# Auto20.net
KiCad netlist of a schematic drawn in EAGLE
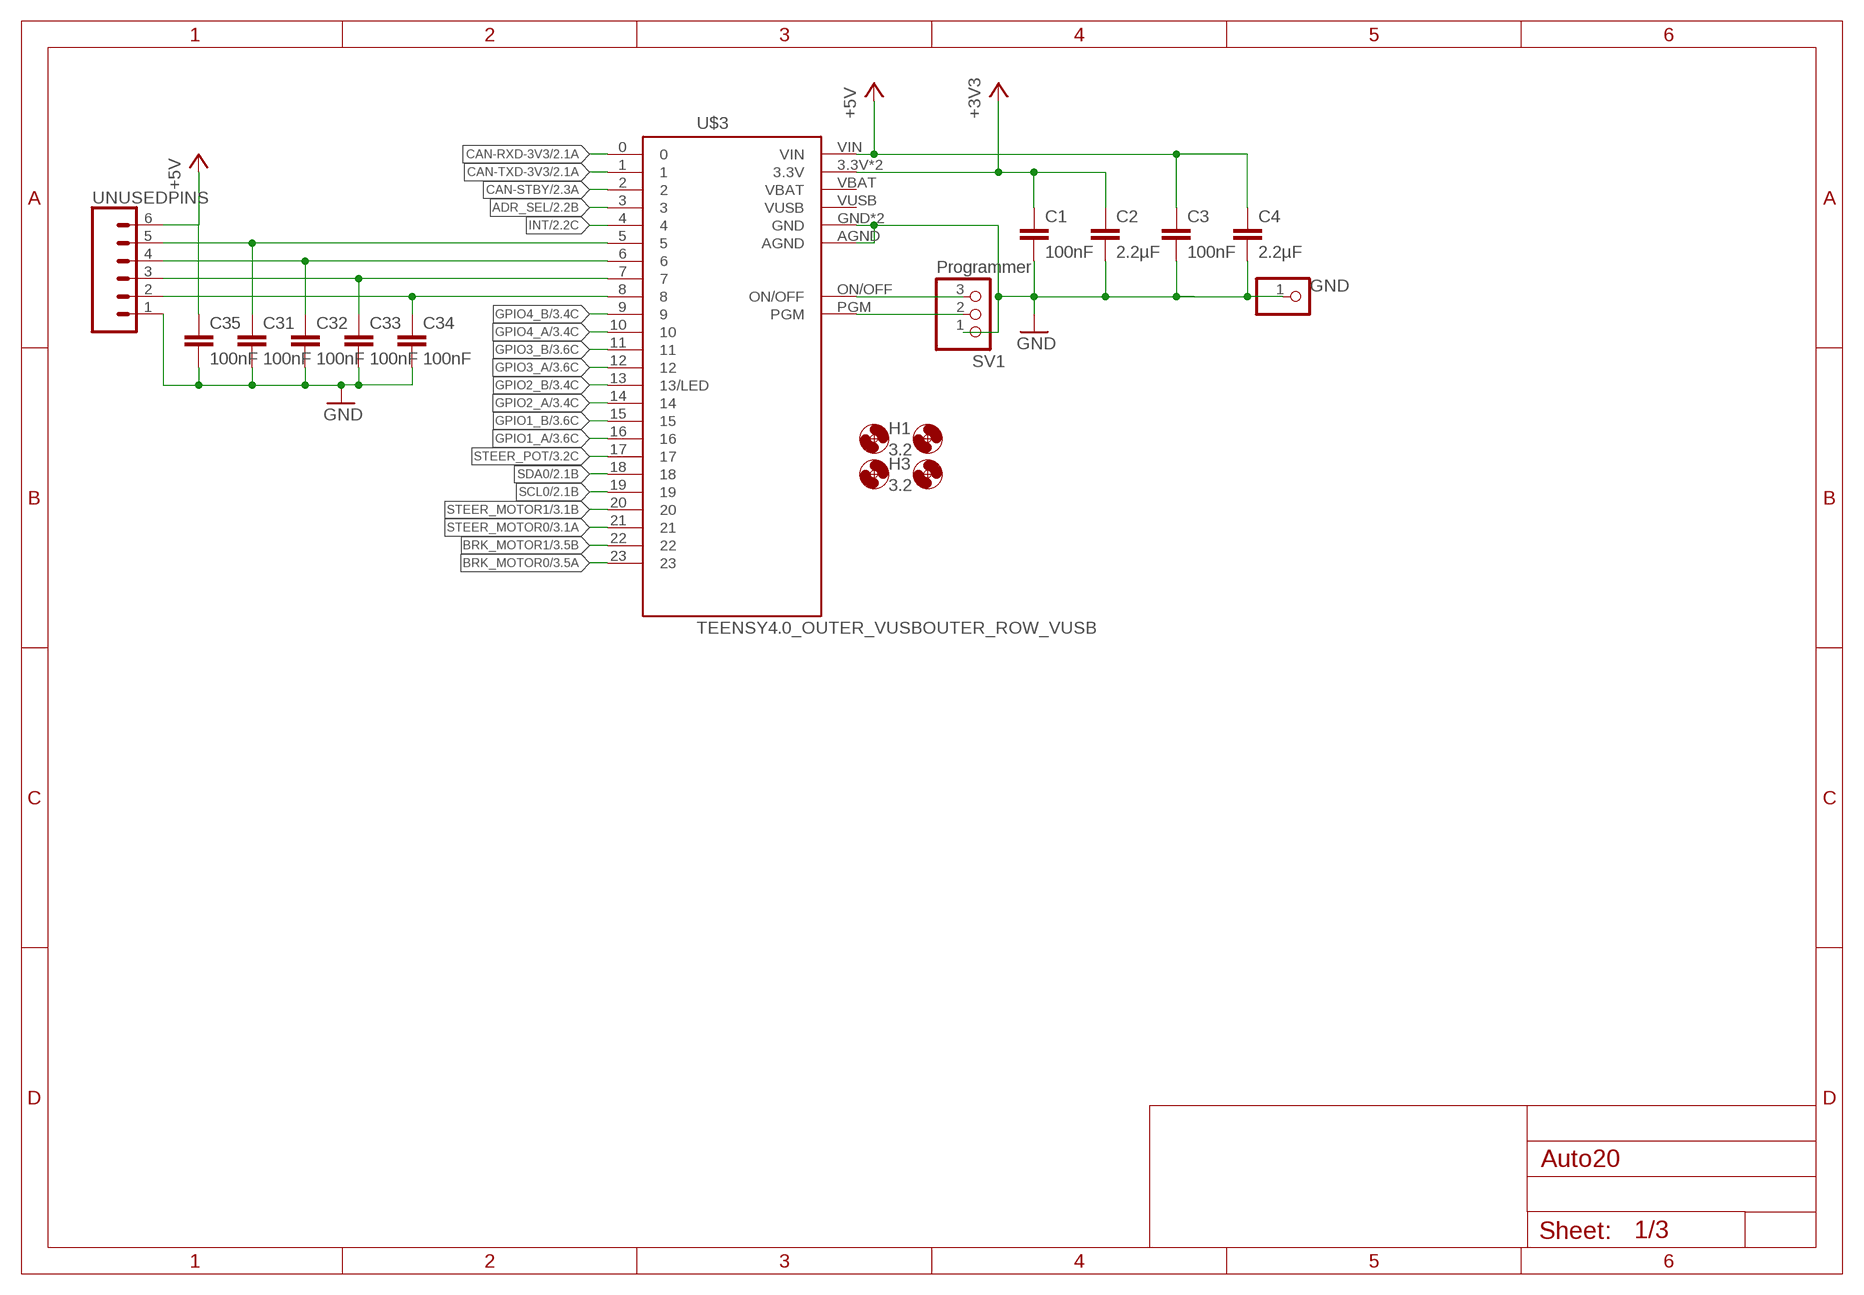
[diagram p0: schematic, sheet 1]
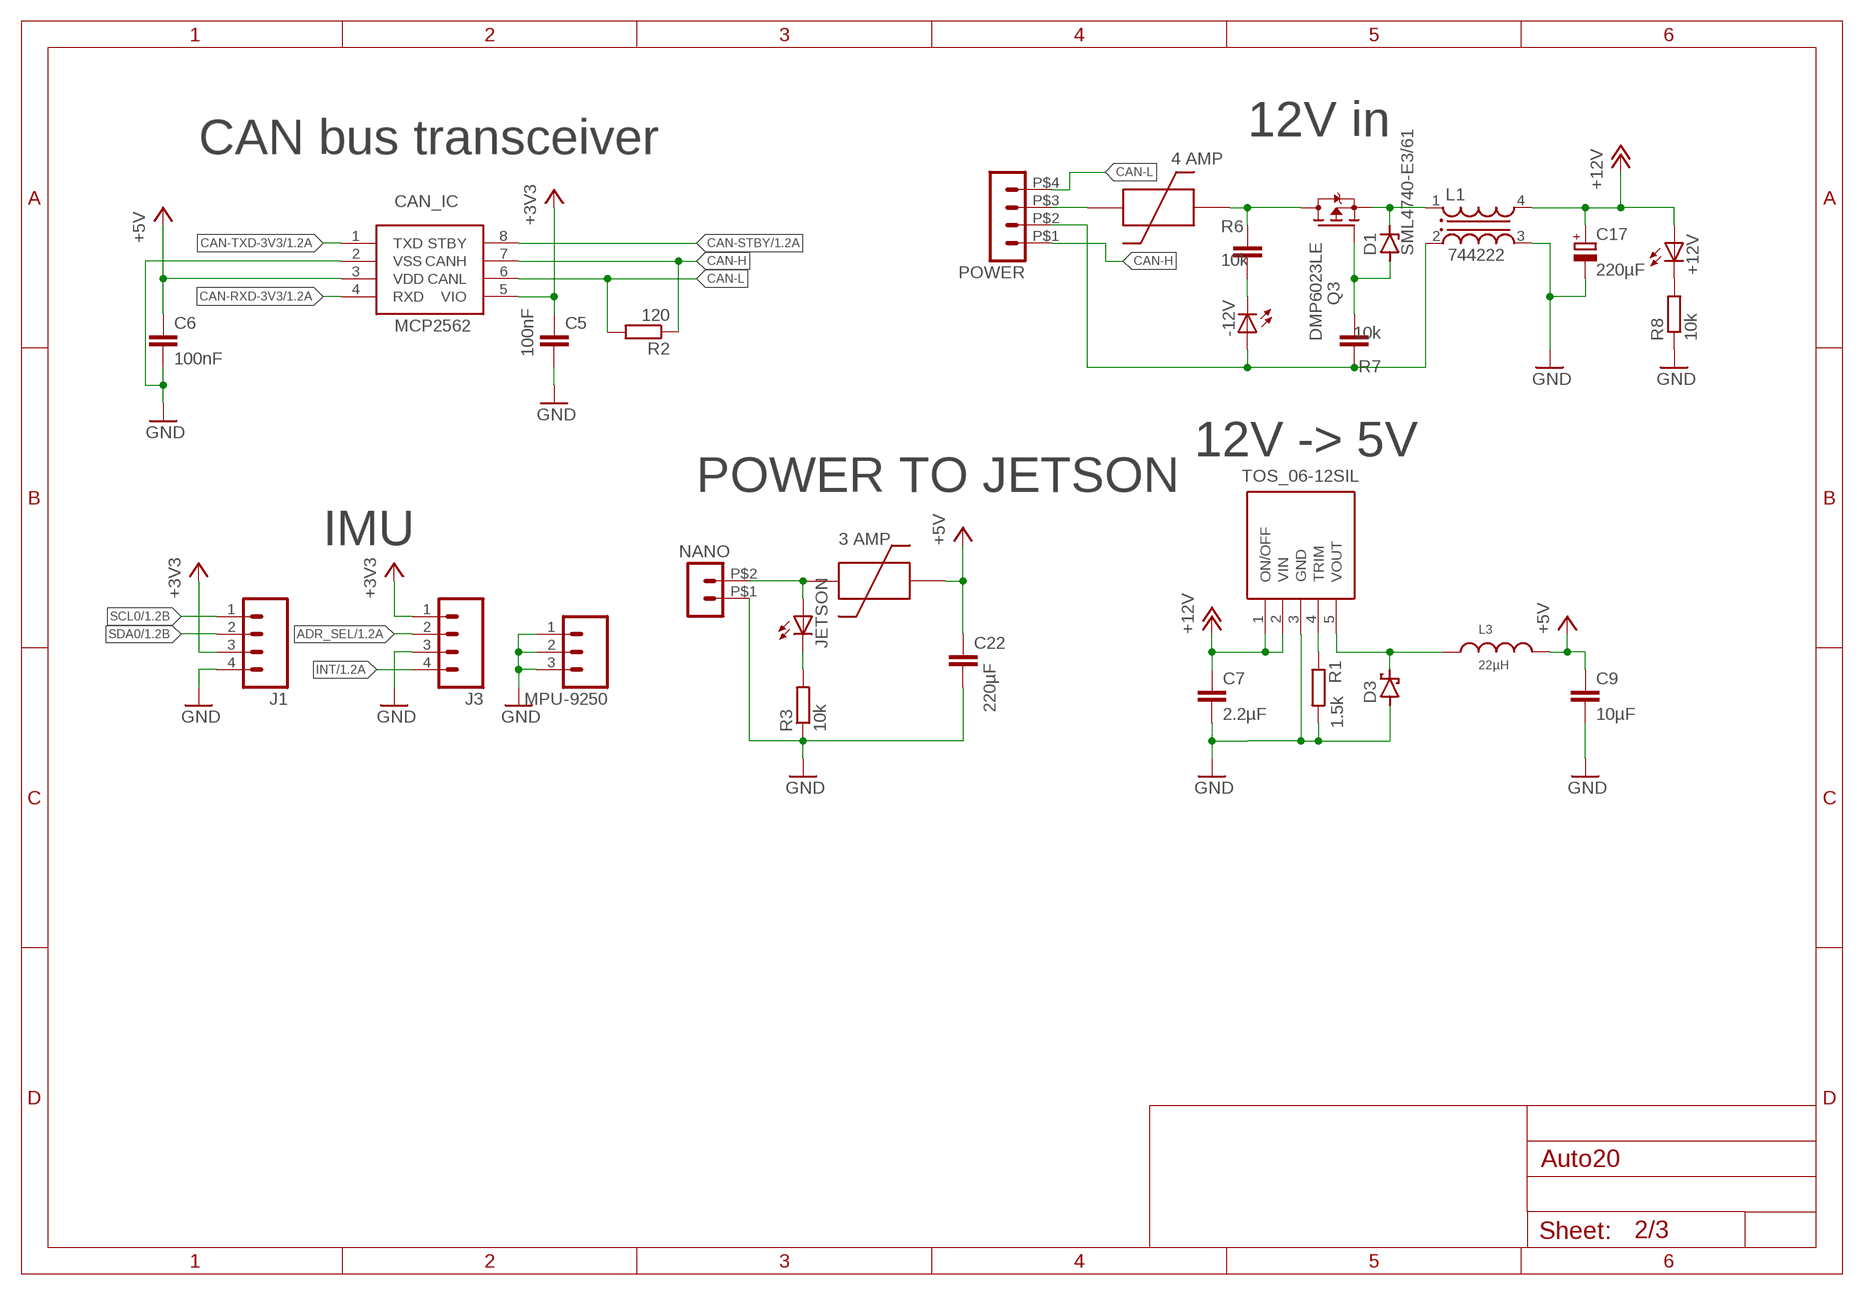
[diagram p1: schematic, sheet 2]
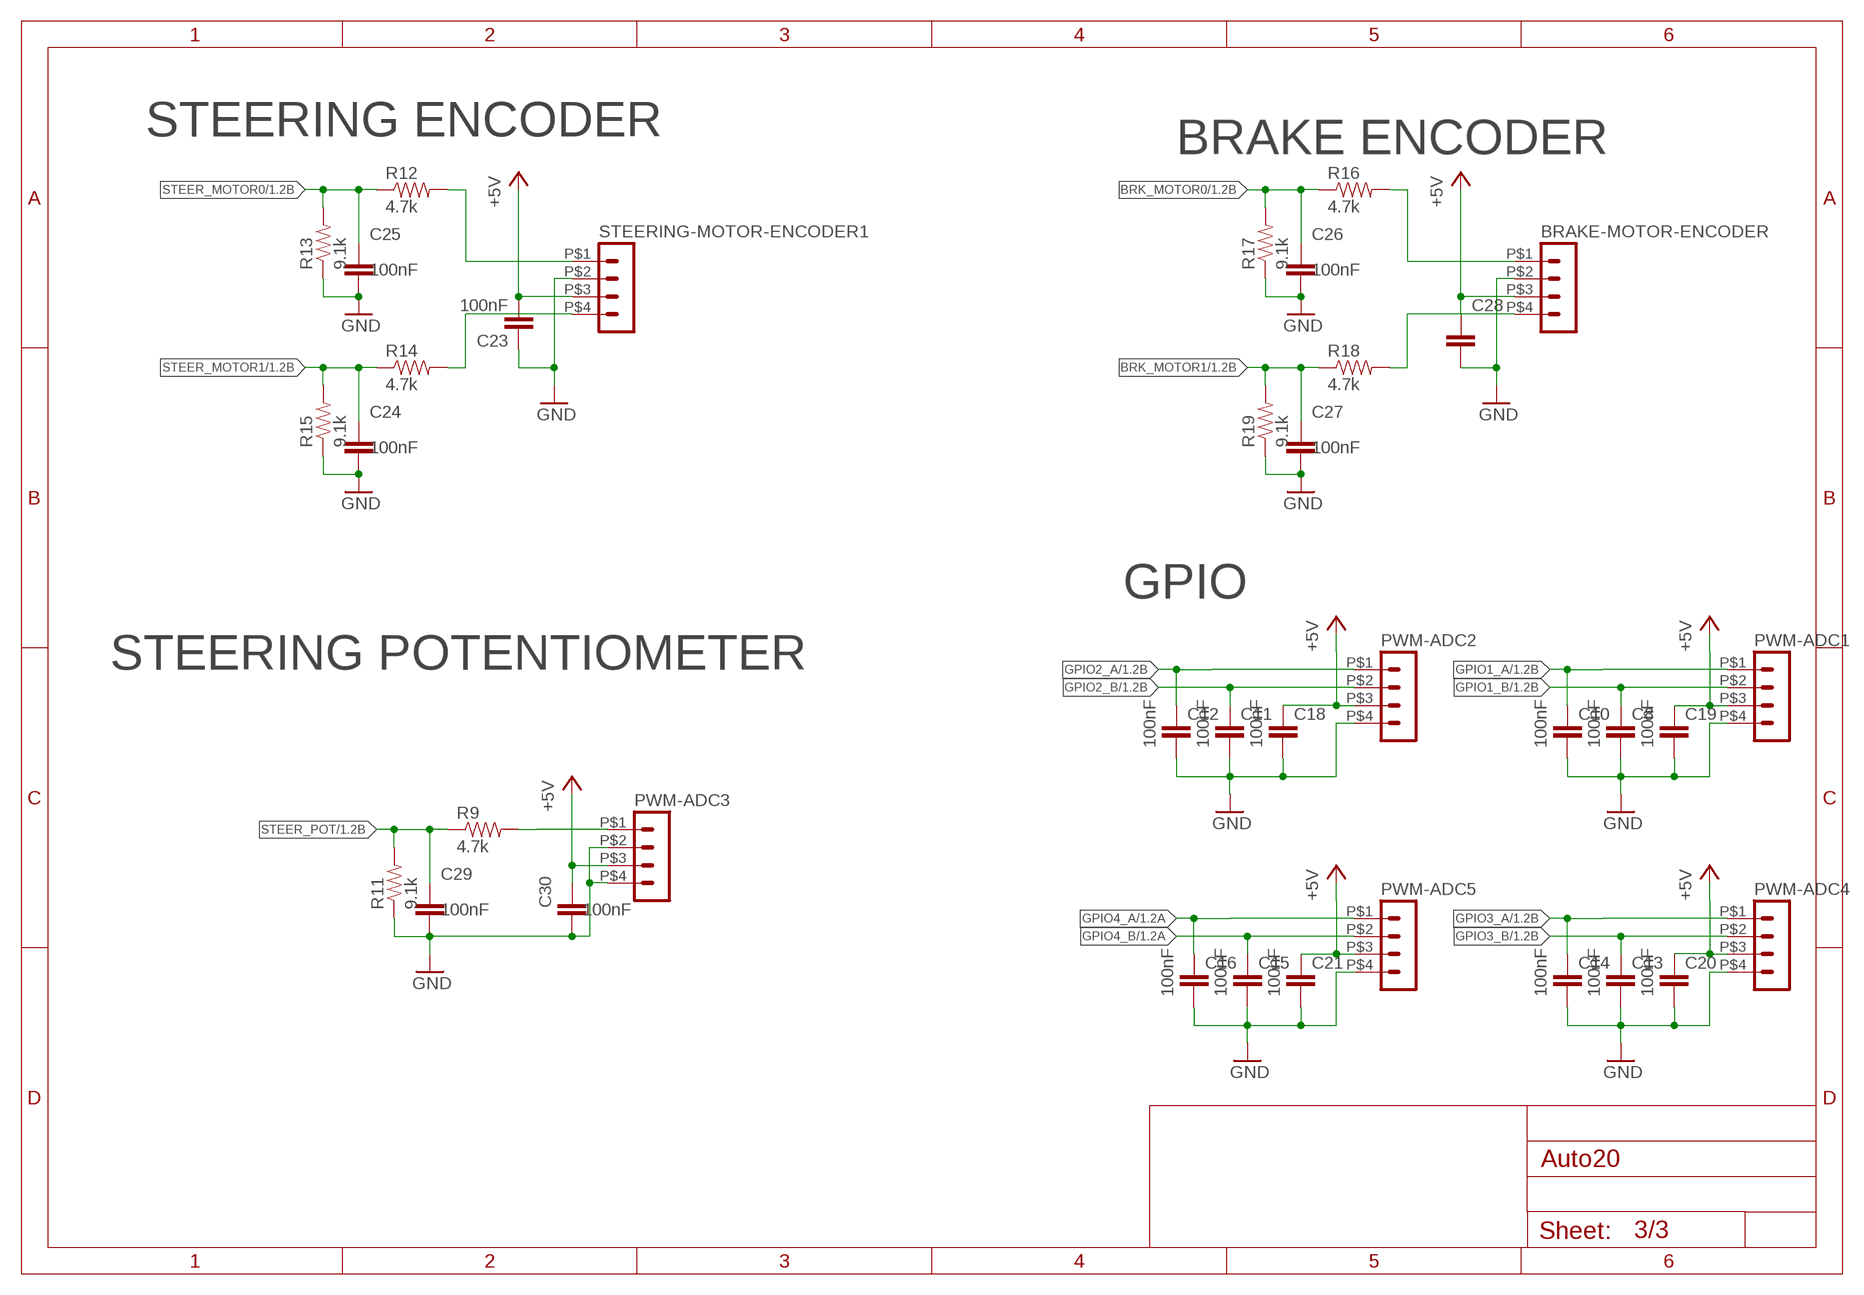
[diagram p2: schematic, sheet 3]

(export (version "E")
  (design (tool "Eeschema 10.0.6"))
  (components
    (comp (ref "+12V")
      (value "LEDSMT1206")
      (footprint "eagle-import:1206")
      (libsource (lib "eagle-import") (part "LEDSMT1206"))
    )
    (comp (ref "-12V")
      (value "LEDSMT1206")
      (footprint "eagle-import:1206")
      (libsource (lib "eagle-import") (part "LEDSMT1206"))
    )
    (comp (ref "C5")
      (value "100nF")
      (footprint "eagle-import:RESC0805_L")
      (libsource (lib "eagle-import") (part "CAPACITOR_0805_L"))
    )
    (comp (ref "C6")
      (value "100nF")
      (footprint "eagle-import:RESC0805_L")
      (libsource (lib "eagle-import") (part "CAPACITOR_0805_L"))
    )
    (comp (ref "C7")
      (value "2.2µF")
      (footprint "eagle-import:C1210")
      (libsource (lib "eagle-import") (part "C-EUC1210"))
    )
    (comp (ref "C9")
      (value "10µF")
      (footprint "eagle-import:C1210")
      (libsource (lib "eagle-import") (part "C-EUC1210"))
    )
    (comp (ref "C17")
      (value "220µF")
      (footprint "eagle-import:PANASONIC_E")
      (libsource (lib "eagle-import") (part "CPOL-EUE"))
    )
    (comp (ref "C22")
      (value "220µF")
      (footprint "eagle-import:C1210")
      (libsource (lib "eagle-import") (part "resistor_348_C-EUC1210"))
    )
    (comp (ref "CAN_IC")
      (value "MCP2562")
      (footprint "eagle-import:SOIC127P600X175-8")
      (libsource (lib "eagle-import") (part "MCP2562"))
    )
    (comp (ref "D1")
      (value "SML4740-E3/61")
      (footprint "eagle-import:DO214AC")
      (libsource (lib "eagle-import") (part "ZENERSMA"))
    )
    (comp (ref "D3")
      (value "SBR1U150SA")
      (footprint "eagle-import:DO214AC")
      (libsource (lib "eagle-import") (part "SBRSMA"))
    )
    (comp (ref "IC1")
      (value "TOS_06-12SIL")
      (footprint "eagle-import:TOS-06-12SIL-6A")
      (fields
        (field (name "MANUFACTURER_PART_NUMBER") "TOS 06-12SIL")
        (field (name "RS_PART_NUMBER") "7066432")
      )
      (libsource (lib "eagle-import") (part "TOS_06-12SIL"))
    )
    (comp (ref "J1")
      (value "M04PTH")
      (footprint "eagle-import:1X04")
      (libsource (lib "eagle-import") (part "M04PTH"))
    )
    (comp (ref "J3")
      (value "M04PTH")
      (footprint "eagle-import:1X04")
      (libsource (lib "eagle-import") (part "M04PTH"))
    )
    (comp (ref "JETSON")
      (value "LEDSMT1206")
      (footprint "eagle-import:1206")
      (libsource (lib "eagle-import") (part "LEDSMT1206"))
    )
    (comp (ref "L1")
      (value "744222")
      (footprint "eagle-import:WE-SL2")
      (libsource (lib "eagle-import") (part "WE-SL2_744222"))
    )
    (comp (ref "L3")
      (value "22µH")
      (footprint "eagle-import:WE-PD_7332_7345_PLASTIC_BASE")
      (libsource (lib "eagle-import") (part "WE-PD_7345_PLASTIC_7447779122"))
    )
    (comp (ref "MPU-9250")
      (value "M03PTH")
      (footprint "eagle-import:1X03")
      (libsource (lib "eagle-import") (part "M03PTH"))
    )
    (comp (ref "NANO")
      (value "HEADER_POS2_43045-0200")
      (footprint "eagle-import:43045-0200")
      (libsource (lib "eagle-import") (part "HEADER_POS2_?43045-0200"))
    )
    (comp (ref "POWER")
      (value "HEADER_POS4_43045-0401")
      (footprint "eagle-import:43045-0400")
      (libsource (lib "eagle-import") (part "HEADER_POS4_?43045-0401"))
    )
    (comp (ref "Q3")
      (value "DMP6023LE")
      (footprint "eagle-import:SOT223")
      (libsource (lib "eagle-import") (part "BSP170P"))
    )
    (comp (ref "R1")
      (value "1.5k")
      (footprint "eagle-import:R0805")
      (libsource (lib "eagle-import") (part "R-EU_R0805"))
    )
    (comp (ref "R2")
      (value "120")
      (footprint "eagle-import:R0603")
      (libsource (lib "eagle-import") (part "R-EU_R0603"))
    )
    (comp (ref "R3")
      (value "10k")
      (footprint "eagle-import:R0805")
      (libsource (lib "eagle-import") (part "R-EU_R0805"))
    )
    (comp (ref "R6")
      (value "10k")
      (footprint "eagle-import:RESC0805_L")
      (libsource (lib "eagle-import") (part "CAPACITOR_0805_L"))
    )
    (comp (ref "R7")
      (value "10k")
      (footprint "eagle-import:RESC0805_L")
      (libsource (lib "eagle-import") (part "CAPACITOR_0805_L"))
    )
    (comp (ref "R8")
      (value "10k")
      (footprint "eagle-import:R0805")
      (libsource (lib "eagle-import") (part "R-EU_R0805"))
    )
    (comp (ref "U$1")
      (value "SMF_OMNI-BLOK_FUSE_BLOCK")
      (footprint "eagle-import:SMF_OMNI-BLOK_FUSE_BLOCK")
      (libsource (lib "eagle-import") (part "SMF_OMNI-BLOK_FUSE_BLOCK"))
    )
    (comp (ref "U$2")
      (value "SMF_OMNI-BLOK_FUSE_BLOCK")
      (footprint "eagle-import:SMF_OMNI-BLOK_FUSE_BLOCK")
      (libsource (lib "eagle-import") (part "SMF_OMNI-BLOK_FUSE_BLOCK"))
    )
    (comp (ref "BRAKE-MOTOR-ENCODER")
      (value "HEADER_POS4_43045-0401")
      (footprint "eagle-import:43045-0400")
      (libsource (lib "eagle-import") (part "HEADER_POS4_?43045-0401"))
    )
    (comp (ref "C8")
      (value "100nF")
      (footprint "eagle-import:RESC0805_L")
      (libsource (lib "eagle-import") (part "CAPACITOR_0805_L"))
    )
    (comp (ref "C10")
      (value "100nF")
      (footprint "eagle-import:RESC0805_L")
      (libsource (lib "eagle-import") (part "CAPACITOR_0805_L"))
    )
    (comp (ref "C11")
      (value "100nF")
      (footprint "eagle-import:RESC0805_L")
      (libsource (lib "eagle-import") (part "CAPACITOR_0805_L"))
    )
    (comp (ref "C12")
      (value "100nF")
      (footprint "eagle-import:RESC0805_L")
      (libsource (lib "eagle-import") (part "CAPACITOR_0805_L"))
    )
    (comp (ref "C13")
      (value "100nF")
      (footprint "eagle-import:RESC0805_L")
      (libsource (lib "eagle-import") (part "CAPACITOR_0805_L"))
    )
    (comp (ref "C14")
      (value "100nF")
      (footprint "eagle-import:RESC0805_L")
      (libsource (lib "eagle-import") (part "CAPACITOR_0805_L"))
    )
    (comp (ref "C15")
      (value "100nF")
      (footprint "eagle-import:RESC0805_L")
      (libsource (lib "eagle-import") (part "CAPACITOR_0805_L"))
    )
    (comp (ref "C16")
      (value "100nF")
      (footprint "eagle-import:RESC0805_L")
      (libsource (lib "eagle-import") (part "CAPACITOR_0805_L"))
    )
    (comp (ref "C18")
      (value "100nF")
      (footprint "eagle-import:RESC0805_L")
      (libsource (lib "eagle-import") (part "CAPACITOR_0805_L"))
    )
    (comp (ref "C19")
      (value "100nF")
      (footprint "eagle-import:RESC0805_L")
      (libsource (lib "eagle-import") (part "CAPACITOR_0805_L"))
    )
    (comp (ref "C20")
      (value "100nF")
      (footprint "eagle-import:RESC0805_L")
      (libsource (lib "eagle-import") (part "CAPACITOR_0805_L"))
    )
    (comp (ref "C21")
      (value "100nF")
      (footprint "eagle-import:RESC0805_L")
      (libsource (lib "eagle-import") (part "CAPACITOR_0805_L"))
    )
    (comp (ref "C23")
      (value "100nF")
      (footprint "eagle-import:RESC0805_L")
      (libsource (lib "eagle-import") (part "CAPACITOR_0805_L"))
    )
    (comp (ref "C24")
      (value "100nF")
      (footprint "eagle-import:RESC0805_L")
      (libsource (lib "eagle-import") (part "CAPACITOR_0805_L"))
    )
    (comp (ref "C25")
      (value "100nF")
      (footprint "eagle-import:RESC0805_L")
      (libsource (lib "eagle-import") (part "CAPACITOR_0805_L"))
    )
    (comp (ref "C26")
      (value "100nF")
      (footprint "eagle-import:RESC0805_L")
      (libsource (lib "eagle-import") (part "CAPACITOR_0805_L"))
    )
    (comp (ref "C27")
      (value "100nF")
      (footprint "eagle-import:RESC0805_L")
      (libsource (lib "eagle-import") (part "CAPACITOR_0805_L"))
    )
    (comp (ref "C28")
      (value "100nF")
      (footprint "eagle-import:RESC0805_L")
      (libsource (lib "eagle-import") (part "CAPACITOR_0805_L"))
    )
    (comp (ref "C29")
      (value "100nF")
      (footprint "eagle-import:RESC0805_L")
      (libsource (lib "eagle-import") (part "CAPACITOR_0805_L"))
    )
    (comp (ref "C30")
      (value "100nF")
      (footprint "eagle-import:RESC0805_L")
      (libsource (lib "eagle-import") (part "CAPACITOR_0805_L"))
    )
    (comp (ref "PWM-ADC1")
      (value "HEADER_POS4_43045-0401")
      (footprint "eagle-import:43045-0400")
      (libsource (lib "eagle-import") (part "HEADER_POS4_?43045-0401"))
    )
    (comp (ref "PWM-ADC2")
      (value "HEADER_POS4_43045-0401")
      (footprint "eagle-import:43045-0400")
      (libsource (lib "eagle-import") (part "HEADER_POS4_?43045-0401"))
    )
    (comp (ref "PWM-ADC3")
      (value "HEADER_POS4_43045-0401")
      (footprint "eagle-import:43045-0400")
      (libsource (lib "eagle-import") (part "HEADER_POS4_?43045-0401"))
    )
    (comp (ref "PWM-ADC4")
      (value "HEADER_POS4_43045-0401")
      (footprint "eagle-import:43045-0400")
      (libsource (lib "eagle-import") (part "HEADER_POS4_?43045-0401"))
    )
    (comp (ref "PWM-ADC5")
      (value "HEADER_POS4_43045-0401")
      (footprint "eagle-import:43045-0400")
      (libsource (lib "eagle-import") (part "HEADER_POS4_?43045-0401"))
    )
    (comp (ref "R9")
      (value "4.7k")
      (footprint "eagle-import:0805")
      (libsource (lib "eagle-import") (part "RESISTOR0805-RES"))
    )
    (comp (ref "R11")
      (value "9.1k")
      (footprint "eagle-import:0805")
      (libsource (lib "eagle-import") (part "RESISTOR0805-RES"))
    )
    (comp (ref "R12")
      (value "4.7k")
      (footprint "eagle-import:0805")
      (libsource (lib "eagle-import") (part "RESISTOR0805-RES"))
    )
    (comp (ref "R13")
      (value "9.1k")
      (footprint "eagle-import:0805")
      (libsource (lib "eagle-import") (part "RESISTOR0805-RES"))
    )
    (comp (ref "R14")
      (value "4.7k")
      (footprint "eagle-import:0805")
      (libsource (lib "eagle-import") (part "RESISTOR0805-RES"))
    )
    (comp (ref "R15")
      (value "9.1k")
      (footprint "eagle-import:0805")
      (libsource (lib "eagle-import") (part "RESISTOR0805-RES"))
    )
    (comp (ref "R16")
      (value "4.7k")
      (footprint "eagle-import:0805")
      (libsource (lib "eagle-import") (part "RESISTOR0805-RES"))
    )
    (comp (ref "R17")
      (value "9.1k")
      (footprint "eagle-import:0805")
      (libsource (lib "eagle-import") (part "RESISTOR0805-RES"))
    )
    (comp (ref "R18")
      (value "4.7k")
      (footprint "eagle-import:0805")
      (libsource (lib "eagle-import") (part "RESISTOR0805-RES"))
    )
    (comp (ref "R19")
      (value "9.1k")
      (footprint "eagle-import:0805")
      (libsource (lib "eagle-import") (part "RESISTOR0805-RES"))
    )
    (comp (ref "STEERING-MOTOR-ENCODER1")
      (value "HEADER_POS4_43045-0401")
      (footprint "eagle-import:43045-0400")
      (libsource (lib "eagle-import") (part "HEADER_POS4_?43045-0401"))
    )
    (comp (ref "C1")
      (value "100nF")
      (footprint "eagle-import:RESC0805_L")
      (libsource (lib "eagle-import") (part "CAPACITOR_0805_L"))
    )
    (comp (ref "C2")
      (value "2.2µF")
      (footprint "eagle-import:C1210")
      (libsource (lib "eagle-import") (part "C-EUC1210"))
    )
    (comp (ref "C3")
      (value "100nF")
      (footprint "eagle-import:RESC0805_L")
      (libsource (lib "eagle-import") (part "CAPACITOR_0805_L"))
    )
    (comp (ref "C4")
      (value "2.2µF")
      (footprint "eagle-import:C1210")
      (libsource (lib "eagle-import") (part "C-EUC1210"))
    )
    (comp (ref "C31")
      (value "100nF")
      (footprint "eagle-import:RESC0805_L")
      (libsource (lib "eagle-import") (part "CAPACITOR_0805_L"))
    )
    (comp (ref "C32")
      (value "100nF")
      (footprint "eagle-import:RESC0805_L")
      (libsource (lib "eagle-import") (part "CAPACITOR_0805_L"))
    )
    (comp (ref "C33")
      (value "100nF")
      (footprint "eagle-import:RESC0805_L")
      (libsource (lib "eagle-import") (part "CAPACITOR_0805_L"))
    )
    (comp (ref "C34")
      (value "100nF")
      (footprint "eagle-import:RESC0805_L")
      (libsource (lib "eagle-import") (part "CAPACITOR_0805_L"))
    )
    (comp (ref "C35")
      (value "100nF")
      (footprint "eagle-import:RESC0805_L")
      (libsource (lib "eagle-import") (part "CAPACITOR_0805_L"))
    )
    (comp (ref "GND")
      (value "PINHD-1X1")
      (footprint "eagle-import:1X01")
      (libsource (lib "eagle-import") (part "PINHD-1X1"))
    )
    (comp (ref "H1")
      (value "3.2")
      (footprint "eagle-import:3,2")
      (libsource (lib "eagle-import") (part "MOUNT-HOLE3.2"))
    )
    (comp (ref "H2")
      (value "3.2")
      (footprint "eagle-import:3,2")
      (libsource (lib "eagle-import") (part "MOUNT-HOLE3.2"))
    )
    (comp (ref "H3")
      (value "3.2")
      (footprint "eagle-import:3,2")
      (libsource (lib "eagle-import") (part "MOUNT-HOLE3.2"))
    )
    (comp (ref "H4")
      (value "3.2")
      (footprint "eagle-import:3,2")
      (libsource (lib "eagle-import") (part "MOUNT-HOLE3.2"))
    )
    (comp (ref "SV1")
      (value "Programmer")
      (footprint "eagle-import:1X03")
      (libsource (lib "eagle-import") (part "PINHD-1X3"))
    )
    (comp (ref "U$3")
      (value "TEENSY4.0_OUTER_VUSBOUTER_ROW_VUSB")
      (footprint "eagle-import:TEENSY_4.0_OUTER_VUSB")
      (libsource (lib "eagle-import") (part "TEENSY4.0_OUTER_VUSBOUTER_ROW_VUSB"))
    )
    (comp (ref "UNUSEDPINS")
      (value "CONN_06LOCK")
      (footprint "eagle-import:1X06_LOCK")
      (libsource (lib "eagle-import") (part "CONN_06LOCK"))
    )
  )
  (nets
    (net (code "1") (name "+3V3") (class "Default")
      (node (ref "C1") (pin "1") (pinfunction "1_1") (pintype "passive"))
      (node (ref "C2") (pin "1") (pinfunction "1_1") (pintype "passive"))
      (node (ref "C5") (pin "1") (pinfunction "1_1") (pintype "passive"))
      (node (ref "CAN_IC") (pin "5") (pinfunction "VIO_5") (pintype "input"))
      (node (ref "J1") (pin "3") (pinfunction "3_3") (pintype "passive"))
      (node (ref "J3") (pin "1") (pinfunction "1_1") (pintype "passive"))
      (node (ref "U$3") (pin "3.3V") (pinfunction "3.3V_3.3V") (pintype "bidirectional"))
      (node (ref "U$3") (pin "3.3V1") (pinfunction "3.3V_3.3V1") (pintype "bidirectional"))
    )
    (net (code "2") (name "+5V") (class "Default")
      (node (ref "BRAKE-MOTOR-ENCODER") (pin "P$3") (pinfunction "3_P$3") (pintype "passive"))
      (node (ref "C18") (pin "1") (pinfunction "1_1") (pintype "passive"))
      (node (ref "C19") (pin "1") (pinfunction "1_1") (pintype "passive"))
      (node (ref "C20") (pin "1") (pinfunction "1_1") (pintype "passive"))
      (node (ref "C21") (pin "1") (pinfunction "1_1") (pintype "passive"))
      (node (ref "C22") (pin "1") (pinfunction "1_1") (pintype "passive"))
      (node (ref "C23") (pin "2") (pinfunction "2_2") (pintype "passive"))
      (node (ref "C28") (pin "1") (pinfunction "1_1") (pintype "passive"))
      (node (ref "C3") (pin "1") (pinfunction "1_1") (pintype "passive"))
      (node (ref "C30") (pin "1") (pinfunction "1_1") (pintype "passive"))
      (node (ref "C35") (pin "1") (pinfunction "1_1") (pintype "passive"))
      (node (ref "C4") (pin "1") (pinfunction "1_1") (pintype "passive"))
      (node (ref "C6") (pin "1") (pinfunction "1_1") (pintype "passive"))
      (node (ref "C9") (pin "1") (pinfunction "1_1") (pintype "passive"))
      (node (ref "CAN_IC") (pin "3") (pinfunction "VDD_3") (pintype "power_in"))
      (node (ref "L3") (pin "2") (pinfunction "2_2") (pintype "passive"))
      (node (ref "PWM-ADC1") (pin "P$3") (pinfunction "3_P$3") (pintype "passive"))
      (node (ref "PWM-ADC2") (pin "P$3") (pinfunction "3_P$3") (pintype "passive"))
      (node (ref "PWM-ADC3") (pin "P$3") (pinfunction "3_P$3") (pintype "passive"))
      (node (ref "PWM-ADC4") (pin "P$3") (pinfunction "3_P$3") (pintype "passive"))
      (node (ref "PWM-ADC5") (pin "P$3") (pinfunction "3_P$3") (pintype "passive"))
      (node (ref "STEERING-MOTOR-ENCODER1") (pin "P$3") (pinfunction "3_P$3") (pintype "passive"))
      (node (ref "U$1") (pin "PIN2") (pinfunction "PIN2_PIN2") (pintype "bidirectional"))
      (node (ref "U$3") (pin "VIN") (pinfunction "VIN_VIN") (pintype "bidirectional"))
      (node (ref "UNUSEDPINS") (pin "6") (pinfunction "6_6") (pintype "passive"))
    )
    (net (code "3") (name "+12V") (class "Default")
      (node (ref "+12V") (pin "A") (pinfunction "A_A") (pintype "passive"))
      (node (ref "C17") (pin "+") (pinfunction "+_+") (pintype "passive"))
      (node (ref "C7") (pin "1") (pinfunction "1_1") (pintype "passive"))
      (node (ref "IC1") (pin "1") (pinfunction "ON/OFF_1") (pintype "bidirectional"))
      (node (ref "IC1") (pin "2") (pinfunction "VIN_2") (pintype "input"))
      (node (ref "L1") (pin "4") (pinfunction "2_4") (pintype "passive"))
    )
    (net (code "4") (name "ADR_SEL") (class "Default")
      (node (ref "J3") (pin "2") (pinfunction "2_2") (pintype "passive"))
      (node (ref "U$3") (pin "3") (pinfunction "3_3") (pintype "bidirectional"))
    )
    (net (code "5") (name "BRK_MOTOR0") (class "Default")
      (node (ref "C26") (pin "1") (pinfunction "1_1") (pintype "passive"))
      (node (ref "R16") (pin "1") (pinfunction "1_1") (pintype "passive"))
      (node (ref "R17") (pin "2") (pinfunction "2_2") (pintype "passive"))
      (node (ref "U$3") (pin "23") (pinfunction "23_23") (pintype "bidirectional"))
    )
    (net (code "6") (name "BRK_MOTOR1") (class "Default")
      (node (ref "C27") (pin "1") (pinfunction "1_1") (pintype "passive"))
      (node (ref "R18") (pin "1") (pinfunction "1_1") (pintype "passive"))
      (node (ref "R19") (pin "2") (pinfunction "2_2") (pintype "passive"))
      (node (ref "U$3") (pin "22") (pinfunction "22_22") (pintype "bidirectional"))
    )
    (net (code "7") (name "CAN-H") (class "Default")
      (node (ref "CAN_IC") (pin "7") (pinfunction "CANH_7") (pintype "bidirectional"))
      (node (ref "POWER") (pin "P$1") (pinfunction "1_P$1") (pintype "passive"))
      (node (ref "R2") (pin "1") (pinfunction "1_1") (pintype "passive"))
    )
    (net (code "8") (name "CAN-L") (class "Default")
      (node (ref "CAN_IC") (pin "6") (pinfunction "CANL_6") (pintype "bidirectional"))
      (node (ref "POWER") (pin "P$4") (pinfunction "4_P$4") (pintype "passive"))
      (node (ref "R2") (pin "2") (pinfunction "2_2") (pintype "passive"))
    )
    (net (code "9") (name "CAN-RXD-3V3") (class "Default")
      (node (ref "CAN_IC") (pin "4") (pinfunction "RXD_4") (pintype "output"))
      (node (ref "U$3") (pin "0") (pinfunction "0_0") (pintype "bidirectional"))
    )
    (net (code "10") (name "CAN-STBY") (class "Default")
      (node (ref "CAN_IC") (pin "8") (pinfunction "STBY_8") (pintype "bidirectional"))
      (node (ref "U$3") (pin "2") (pinfunction "2_2") (pintype "bidirectional"))
    )
    (net (code "11") (name "CAN-TXD-3V3") (class "Default")
      (node (ref "CAN_IC") (pin "1") (pinfunction "TXD_1") (pintype "input"))
      (node (ref "U$3") (pin "1") (pinfunction "1_1") (pintype "bidirectional"))
    )
    (net (code "12") (name "GND") (class "Default")
      (node (ref "BRAKE-MOTOR-ENCODER") (pin "P$2") (pinfunction "2_P$2") (pintype "passive"))
      (node (ref "C1") (pin "2") (pinfunction "2_2") (pintype "passive"))
      (node (ref "C10") (pin "2") (pinfunction "2_2") (pintype "passive"))
      (node (ref "C11") (pin "2") (pinfunction "2_2") (pintype "passive"))
      (node (ref "C12") (pin "2") (pinfunction "2_2") (pintype "passive"))
      (node (ref "C13") (pin "2") (pinfunction "2_2") (pintype "passive"))
      (node (ref "C14") (pin "2") (pinfunction "2_2") (pintype "passive"))
      (node (ref "C15") (pin "2") (pinfunction "2_2") (pintype "passive"))
      (node (ref "C16") (pin "2") (pinfunction "2_2") (pintype "passive"))
      (node (ref "C17") (pin "-") (pinfunction "-_-") (pintype "passive"))
      (node (ref "C18") (pin "2") (pinfunction "2_2") (pintype "passive"))
      (node (ref "C19") (pin "2") (pinfunction "2_2") (pintype "passive"))
      (node (ref "C2") (pin "2") (pinfunction "2_2") (pintype "passive"))
      (node (ref "C20") (pin "2") (pinfunction "2_2") (pintype "passive"))
      (node (ref "C21") (pin "2") (pinfunction "2_2") (pintype "passive"))
      (node (ref "C22") (pin "2") (pinfunction "2_2") (pintype "passive"))
      (node (ref "C23") (pin "1") (pinfunction "1_1") (pintype "passive"))
      (node (ref "C24") (pin "2") (pinfunction "2_2") (pintype "passive"))
      (node (ref "C25") (pin "2") (pinfunction "2_2") (pintype "passive"))
      (node (ref "C26") (pin "2") (pinfunction "2_2") (pintype "passive"))
      (node (ref "C27") (pin "2") (pinfunction "2_2") (pintype "passive"))
      (node (ref "C28") (pin "2") (pinfunction "2_2") (pintype "passive"))
      (node (ref "C29") (pin "2") (pinfunction "2_2") (pintype "passive"))
      (node (ref "C3") (pin "2") (pinfunction "2_2") (pintype "passive"))
      (node (ref "C30") (pin "2") (pinfunction "2_2") (pintype "passive"))
      (node (ref "C31") (pin "2") (pinfunction "2_2") (pintype "passive"))
      (node (ref "C32") (pin "2") (pinfunction "2_2") (pintype "passive"))
      (node (ref "C33") (pin "2") (pinfunction "2_2") (pintype "passive"))
      (node (ref "C34") (pin "2") (pinfunction "2_2") (pintype "passive"))
      (node (ref "C35") (pin "2") (pinfunction "2_2") (pintype "passive"))
      (node (ref "C4") (pin "2") (pinfunction "2_2") (pintype "passive"))
      (node (ref "C5") (pin "2") (pinfunction "2_2") (pintype "passive"))
      (node (ref "C6") (pin "2") (pinfunction "2_2") (pintype "passive"))
      (node (ref "C7") (pin "2") (pinfunction "2_2") (pintype "passive"))
      (node (ref "C8") (pin "2") (pinfunction "2_2") (pintype "passive"))
      (node (ref "C9") (pin "2") (pinfunction "2_2") (pintype "passive"))
      (node (ref "CAN_IC") (pin "2") (pinfunction "VSS_2") (pintype "power_in"))
      (node (ref "D3") (pin "A") (pinfunction "A_A") (pintype "passive"))
      (node (ref "GND") (pin "1") (pinfunction "1_1") (pintype "passive"))
      (node (ref "IC1") (pin "3") (pinfunction "GND_3") (pintype "power_in"))
      (node (ref "J1") (pin "4") (pinfunction "4_4") (pintype "passive"))
      (node (ref "J3") (pin "3") (pinfunction "3_3") (pintype "passive"))
      (node (ref "L1") (pin "3") (pinfunction "3_3") (pintype "passive"))
      (node (ref "MPU-9250") (pin "1") (pinfunction "1_1") (pintype "passive"))
      (node (ref "MPU-9250") (pin "2") (pinfunction "2_2") (pintype "passive"))
      (node (ref "MPU-9250") (pin "3") (pinfunction "3_3") (pintype "passive"))
      (node (ref "NANO") (pin "P$1") (pinfunction "1_P$1") (pintype "passive"))
      (node (ref "PWM-ADC1") (pin "P$4") (pinfunction "4_P$4") (pintype "passive"))
      (node (ref "PWM-ADC2") (pin "P$4") (pinfunction "4_P$4") (pintype "passive"))
      (node (ref "PWM-ADC3") (pin "P$2") (pinfunction "2_P$2") (pintype "passive"))
      (node (ref "PWM-ADC3") (pin "P$4") (pinfunction "4_P$4") (pintype "passive"))
      (node (ref "PWM-ADC4") (pin "P$4") (pinfunction "4_P$4") (pintype "passive"))
      (node (ref "PWM-ADC5") (pin "P$4") (pinfunction "4_P$4") (pintype "passive"))
      (node (ref "R1") (pin "2") (pinfunction "2_2") (pintype "passive"))
      (node (ref "R11") (pin "1") (pinfunction "1_1") (pintype "passive"))
      (node (ref "R13") (pin "1") (pinfunction "1_1") (pintype "passive"))
      (node (ref "R15") (pin "1") (pinfunction "1_1") (pintype "passive"))
      (node (ref "R17") (pin "1") (pinfunction "1_1") (pintype "passive"))
      (node (ref "R19") (pin "1") (pinfunction "1_1") (pintype "passive"))
      (node (ref "R3") (pin "1") (pinfunction "1_1") (pintype "passive"))
      (node (ref "R8") (pin "1") (pinfunction "1_1") (pintype "passive"))
      (node (ref "STEERING-MOTOR-ENCODER1") (pin "P$2") (pinfunction "2_P$2") (pintype "passive"))
      (node (ref "SV1") (pin "1") (pinfunction "1_1") (pintype "passive"))
      (node (ref "U$3") (pin "AGND") (pinfunction "AGND_AGND") (pintype "bidirectional"))
      (node (ref "U$3") (pin "GND") (pinfunction "GND_GND") (pintype "bidirectional"))
      (node (ref "U$3") (pin "GND1") (pinfunction "GND_GND1") (pintype "bidirectional"))
      (node (ref "UNUSEDPINS") (pin "1") (pinfunction "1_1") (pintype "passive"))
    )
    (net (code "13") (name "GPIO1_A") (class "Default")
      (node (ref "C10") (pin "1") (pinfunction "1_1") (pintype "passive"))
      (node (ref "PWM-ADC1") (pin "P$1") (pinfunction "1_P$1") (pintype "passive"))
      (node (ref "U$3") (pin "16") (pinfunction "16_16") (pintype "bidirectional"))
    )
    (net (code "14") (name "GPIO1_B") (class "Default")
      (node (ref "C8") (pin "1") (pinfunction "1_1") (pintype "passive"))
      (node (ref "PWM-ADC1") (pin "P$2") (pinfunction "2_P$2") (pintype "passive"))
      (node (ref "U$3") (pin "15") (pinfunction "15_15") (pintype "bidirectional"))
    )
    (net (code "15") (name "GPIO2_A") (class "Default")
      (node (ref "C12") (pin "1") (pinfunction "1_1") (pintype "passive"))
      (node (ref "PWM-ADC2") (pin "P$1") (pinfunction "1_P$1") (pintype "passive"))
      (node (ref "U$3") (pin "14") (pinfunction "14_14") (pintype "bidirectional"))
    )
    (net (code "16") (name "GPIO2_B") (class "Default")
      (node (ref "C11") (pin "1") (pinfunction "1_1") (pintype "passive"))
      (node (ref "PWM-ADC2") (pin "P$2") (pinfunction "2_P$2") (pintype "passive"))
      (node (ref "U$3") (pin "13") (pinfunction "13/LED_13") (pintype "bidirectional"))
    )
    (net (code "17") (name "GPIO3_A") (class "Default")
      (node (ref "C14") (pin "1") (pinfunction "1_1") (pintype "passive"))
      (node (ref "PWM-ADC4") (pin "P$1") (pinfunction "1_P$1") (pintype "passive"))
      (node (ref "U$3") (pin "12") (pinfunction "12_12") (pintype "bidirectional"))
    )
    (net (code "18") (name "GPIO3_B") (class "Default")
      (node (ref "C13") (pin "1") (pinfunction "1_1") (pintype "passive"))
      (node (ref "PWM-ADC4") (pin "P$2") (pinfunction "2_P$2") (pintype "passive"))
      (node (ref "U$3") (pin "11") (pinfunction "11_11") (pintype "bidirectional"))
    )
    (net (code "19") (name "GPIO4_A") (class "Default")
      (node (ref "C16") (pin "1") (pinfunction "1_1") (pintype "passive"))
      (node (ref "PWM-ADC5") (pin "P$1") (pinfunction "1_P$1") (pintype "passive"))
      (node (ref "U$3") (pin "10") (pinfunction "10_10") (pintype "bidirectional"))
    )
    (net (code "20") (name "GPIO4_B") (class "Default")
      (node (ref "C15") (pin "1") (pinfunction "1_1") (pintype "passive"))
      (node (ref "PWM-ADC5") (pin "P$2") (pinfunction "2_P$2") (pintype "passive"))
      (node (ref "U$3") (pin "9") (pinfunction "9_9") (pintype "bidirectional"))
    )
    (net (code "21") (name "INT") (class "Default")
      (node (ref "J3") (pin "4") (pinfunction "4_4") (pintype "passive"))
      (node (ref "U$3") (pin "4") (pinfunction "4_4") (pintype "bidirectional"))
    )
    (net (code "22") (name "Net-(+12V-PadC)") (class "Default")
      (node (ref "+12V") (pin "C") (pinfunction "C_C") (pintype "passive"))
      (node (ref "R8") (pin "2") (pinfunction "2_2") (pintype "passive"))
    )
    (net (code "23") (name "Net-(-12V-PadC)") (class "Default")
      (node (ref "-12V") (pin "C") (pinfunction "C_C") (pintype "passive"))
      (node (ref "R6") (pin "2") (pinfunction "2_2") (pintype "passive"))
    )
    (net (code "24") (name "Net-(BRAKE-MOTOR-ENCODER-1)") (class "Default")
      (node (ref "BRAKE-MOTOR-ENCODER") (pin "P$1") (pinfunction "1_P$1") (pintype "passive"))
      (node (ref "R16") (pin "2") (pinfunction "2_2") (pintype "passive"))
    )
    (net (code "25") (name "Net-(BRAKE-MOTOR-ENCODER-4)") (class "Default")
      (node (ref "BRAKE-MOTOR-ENCODER") (pin "P$4") (pinfunction "4_P$4") (pintype "passive"))
      (node (ref "R18") (pin "2") (pinfunction "2_2") (pintype "passive"))
    )
    (net (code "26") (name "Net-(C31-Pad1)") (class "Default")
      (node (ref "C31") (pin "1") (pinfunction "1_1") (pintype "passive"))
      (node (ref "U$3") (pin "5") (pinfunction "5_5") (pintype "bidirectional"))
      (node (ref "UNUSEDPINS") (pin "5") (pinfunction "5_5") (pintype "passive"))
    )
    (net (code "27") (name "Net-(C32-Pad1)") (class "Default")
      (node (ref "C32") (pin "1") (pinfunction "1_1") (pintype "passive"))
      (node (ref "U$3") (pin "6") (pinfunction "6_6") (pintype "bidirectional"))
      (node (ref "UNUSEDPINS") (pin "4") (pinfunction "4_4") (pintype "passive"))
    )
    (net (code "28") (name "Net-(C33-Pad1)") (class "Default")
      (node (ref "C33") (pin "1") (pinfunction "1_1") (pintype "passive"))
      (node (ref "U$3") (pin "7") (pinfunction "7_7") (pintype "bidirectional"))
      (node (ref "UNUSEDPINS") (pin "3") (pinfunction "3_3") (pintype "passive"))
    )
    (net (code "29") (name "Net-(C34-Pad1)") (class "Default")
      (node (ref "C34") (pin "1") (pinfunction "1_1") (pintype "passive"))
      (node (ref "U$3") (pin "8") (pinfunction "8_8") (pintype "bidirectional"))
      (node (ref "UNUSEDPINS") (pin "2") (pinfunction "2_2") (pintype "passive"))
    )
    (net (code "30") (name "Net-(IC1-TRIM)") (class "Default")
      (node (ref "IC1") (pin "4") (pinfunction "TRIM_4") (pintype "bidirectional"))
      (node (ref "R1") (pin "1") (pinfunction "1_1") (pintype "passive"))
    )
    (net (code "31") (name "Net-(IC1-VOUT)") (class "Default")
      (node (ref "D3") (pin "C") (pinfunction "C_C") (pintype "passive"))
      (node (ref "IC1") (pin "5") (pinfunction "VOUT_5") (pintype "output"))
      (node (ref "L3") (pin "1") (pinfunction "1_1") (pintype "passive"))
    )
    (net (code "32") (name "Net-(JETSON-PadC)") (class "Default")
      (node (ref "JETSON") (pin "C") (pinfunction "C_C") (pintype "passive"))
      (node (ref "R3") (pin "2") (pinfunction "2_2") (pintype "passive"))
    )
    (net (code "33") (name "Net-(L1-4)") (class "Default")
      (node (ref "-12V") (pin "A") (pinfunction "A_A") (pintype "passive"))
      (node (ref "L1") (pin "2") (pinfunction "4_2") (pintype "passive"))
      (node (ref "POWER") (pin "P$2") (pinfunction "2_P$2") (pintype "passive"))
      (node (ref "R7") (pin "1") (pinfunction "1_1") (pintype "passive"))
    )
    (net (code "34") (name "Net-(NANO-2)") (class "Default")
      (node (ref "JETSON") (pin "A") (pinfunction "A_A") (pintype "passive"))
      (node (ref "NANO") (pin "P$2") (pinfunction "2_P$2") (pintype "passive"))
      (node (ref "U$1") (pin "PIN1") (pinfunction "PIN1_PIN1") (pintype "bidirectional"))
    )
    (net (code "35") (name "Net-(POWER-3)") (class "Default")
      (node (ref "POWER") (pin "P$3") (pinfunction "3_P$3") (pintype "passive"))
      (node (ref "U$2") (pin "PIN1") (pinfunction "PIN1_PIN1") (pintype "bidirectional"))
    )
    (net (code "36") (name "Net-(PWM-ADC3-1)") (class "Default")
      (node (ref "PWM-ADC3") (pin "P$1") (pinfunction "1_P$1") (pintype "passive"))
      (node (ref "R9") (pin "2") (pinfunction "2_2") (pintype "passive"))
    )
    (net (code "37") (name "Net-(Q3-D-Pad2)") (class "Default")
      (node (ref "Q3") (pin "2") (pinfunction "D_2") (pintype "passive"))
      (node (ref "Q3") (pin "4") (pinfunction "D_4") (pintype "passive"))
      (node (ref "R6") (pin "1") (pinfunction "1_1") (pintype "passive"))
      (node (ref "U$2") (pin "PIN2") (pinfunction "PIN2_PIN2") (pintype "bidirectional"))
    )
    (net (code "38") (name "Net-(Q3-G)") (class "Default")
      (node (ref "D1") (pin "A") (pinfunction "A_A") (pintype "passive"))
      (node (ref "Q3") (pin "1") (pinfunction "G_1") (pintype "passive"))
      (node (ref "R7") (pin "2") (pinfunction "2_2") (pintype "passive"))
    )
    (net (code "39") (name "Net-(Q3-S)") (class "Default")
      (node (ref "D1") (pin "C") (pinfunction "C_C") (pintype "passive"))
      (node (ref "L1") (pin "1") (pinfunction "1_1") (pintype "passive"))
      (node (ref "Q3") (pin "3") (pinfunction "S_3") (pintype "passive"))
    )
    (net (code "40") (name "Net-(STEERING-MOTOR-ENCODER1-1)") (class "Default")
      (node (ref "R12") (pin "2") (pinfunction "2_2") (pintype "passive"))
      (node (ref "STEERING-MOTOR-ENCODER1") (pin "P$1") (pinfunction "1_P$1") (pintype "passive"))
    )
    (net (code "41") (name "Net-(STEERING-MOTOR-ENCODER1-4)") (class "Default")
      (node (ref "R14") (pin "2") (pinfunction "2_2") (pintype "passive"))
      (node (ref "STEERING-MOTOR-ENCODER1") (pin "P$4") (pinfunction "4_P$4") (pintype "passive"))
    )
    (net (code "42") (name "Net-(SV1-Pad2)") (class "Default")
      (node (ref "SV1") (pin "2") (pinfunction "2_2") (pintype "passive"))
      (node (ref "U$3") (pin "PGM") (pinfunction "PGM_PGM") (pintype "bidirectional"))
    )
    (net (code "43") (name "Net-(SV1-Pad3)") (class "Default")
      (node (ref "SV1") (pin "3") (pinfunction "3_3") (pintype "passive"))
      (node (ref "U$3") (pin "ON/OFF") (pinfunction "ON/OFF_ON/OFF") (pintype "bidirectional"))
    )
    (net (code "44") (name "SCL0") (class "Default")
      (node (ref "J1") (pin "1") (pinfunction "1_1") (pintype "passive"))
      (node (ref "U$3") (pin "19") (pinfunction "19_19") (pintype "bidirectional"))
    )
    (net (code "45") (name "SDA0") (class "Default")
      (node (ref "J1") (pin "2") (pinfunction "2_2") (pintype "passive"))
      (node (ref "U$3") (pin "18") (pinfunction "18_18") (pintype "bidirectional"))
    )
    (net (code "46") (name "STEER_MOTOR0") (class "Default")
      (node (ref "C25") (pin "1") (pinfunction "1_1") (pintype "passive"))
      (node (ref "R12") (pin "1") (pinfunction "1_1") (pintype "passive"))
      (node (ref "R13") (pin "2") (pinfunction "2_2") (pintype "passive"))
      (node (ref "U$3") (pin "21") (pinfunction "21_21") (pintype "bidirectional"))
    )
    (net (code "47") (name "STEER_MOTOR1") (class "Default")
      (node (ref "C24") (pin "1") (pinfunction "1_1") (pintype "passive"))
      (node (ref "R14") (pin "1") (pinfunction "1_1") (pintype "passive"))
      (node (ref "R15") (pin "2") (pinfunction "2_2") (pintype "passive"))
      (node (ref "U$3") (pin "20") (pinfunction "20_20") (pintype "bidirectional"))
    )
    (net (code "48") (name "STEER_POT") (class "Default")
      (node (ref "C29") (pin "1") (pinfunction "1_1") (pintype "passive"))
      (node (ref "R11") (pin "2") (pinfunction "2_2") (pintype "passive"))
      (node (ref "R9") (pin "1") (pinfunction "1_1") (pintype "passive"))
      (node (ref "U$3") (pin "17") (pinfunction "17_17") (pintype "bidirectional"))
    )
    (net (code "49") (name "unconnected-(U$3-PadVBAT)") (class "Default")
      (node (ref "U$3") (pin "VBAT") (pinfunction "VBAT_VBAT") (pintype "bidirectional"))
    )
    (net (code "50") (name "unconnected-(U$3-PadVUSB)") (class "Default")
      (node (ref "U$3") (pin "VUSB") (pinfunction "VUSB_VUSB") (pintype "bidirectional"))
    )
  )
)
